# Tx.net
KiCad netlist of a schematic drawn in Altium Designer
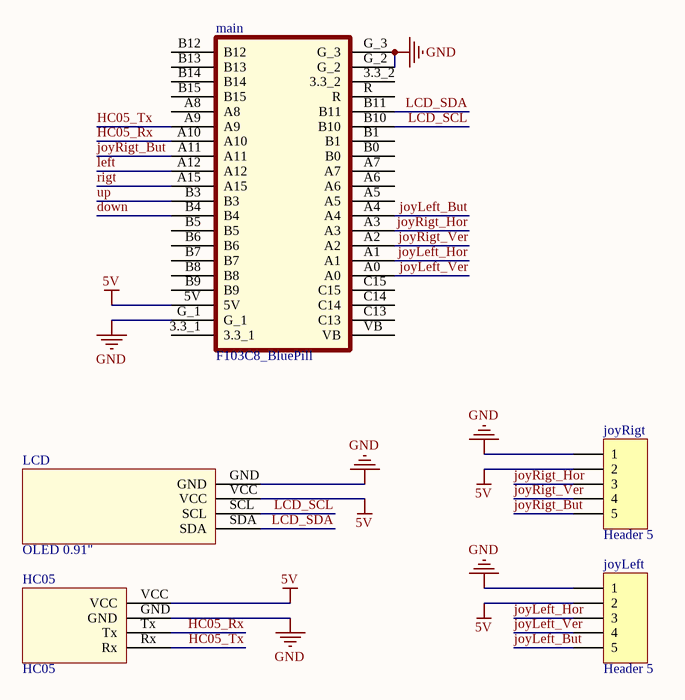
[diagram p0: Tx.SchDoc]

(export (version "E")
  (design (tool "Eeschema 10.0.6"))
  (components
    (comp (ref "HC05") (value "HC05") (footprint "HC05") (libsource (lib "RF-Bluetooth") (part "HC05")))
    (comp (ref "joyLeft")
      (value "Header 5")
      (footprint "HDR1X5")
      (description "Header, 5-Pin")
      (fields (field (name "PUBLISHER") "Altium Limited"))
      (libsource (lib "Miscellaneous Connectors") (part "Header 5"))
    )
    (comp (ref "joyRigt")
      (value "Header 5")
      (footprint "HDR1X5")
      (description "Header, 5-Pin")
      (fields (field (name "PUBLISHER") "Altium Limited"))
      (libsource (lib "Miscellaneous Connectors") (part "Header 5"))
    )
    (comp (ref "LCD")
      (value "OLED 0.91\"")
      (footprint "OLED 0.91\"")
      (libsource (lib "Screen") (part "OLED 0.91{dblquote}"))
    )
    (comp (ref "main")
      (value "F103C8_BluePill")
      (footprint "F103_BluePill")
      (libsource (lib "STM32KIT") (part "F103C8_BluePill"))
    )
  )
  (nets
    (net (code "1") (name "/HC05_Rx") (class "Default")
      (node (ref "HC05") (pin "Tx") (pinfunction "Tx_Tx") (pintype "passive"))
      (node (ref "main") (pin "A10") (pinfunction "A10_A10") (pintype "passive"))
    )
    (net (code "2") (name "/HC05_Tx") (class "Default")
      (node (ref "HC05") (pin "Rx") (pinfunction "Rx_Rx") (pintype "passive"))
      (node (ref "main") (pin "A9") (pinfunction "A9_A9") (pintype "passive"))
    )
    (net (code "3") (name "/LCD_SCL") (class "Default")
      (node (ref "LCD") (pin "SCL") (pinfunction "SCL_SCL") (pintype "passive"))
      (node (ref "main") (pin "B10") (pinfunction "B10_B10") (pintype "passive"))
    )
    (net (code "4") (name "/LCD_SDA") (class "Default")
      (node (ref "LCD") (pin "SDA") (pinfunction "SDA_SDA") (pintype "passive"))
      (node (ref "main") (pin "B11") (pinfunction "B11_B11") (pintype "passive"))
    )
    (net (code "5") (name "/down") (class "Default")
      (node (ref "main") (pin "B4") (pinfunction "B4_B4") (pintype "passive"))
    )
    (net (code "6") (name "/joyLeft_But") (class "Default")
      (node (ref "joyLeft") (pin "5") (pinfunction "5_5") (pintype "passive"))
      (node (ref "main") (pin "A4") (pinfunction "A4_A4") (pintype "passive"))
    )
    (net (code "7") (name "/joyLeft_Hor") (class "Default")
      (node (ref "joyLeft") (pin "3") (pinfunction "3_3") (pintype "passive"))
      (node (ref "main") (pin "A1") (pinfunction "A1_A1") (pintype "passive"))
    )
    (net (code "8") (name "/joyLeft_Ver") (class "Default")
      (node (ref "joyLeft") (pin "4") (pinfunction "4_4") (pintype "passive"))
      (node (ref "main") (pin "A0") (pinfunction "A0_A0") (pintype "passive"))
    )
    (net (code "9") (name "/joyRigt_But") (class "Default")
      (node (ref "joyRigt") (pin "5") (pinfunction "5_5") (pintype "passive"))
      (node (ref "main") (pin "A11") (pinfunction "A11_A11") (pintype "passive"))
    )
    (net (code "10") (name "/joyRigt_Hor") (class "Default")
      (node (ref "joyRigt") (pin "3") (pinfunction "3_3") (pintype "passive"))
      (node (ref "main") (pin "A3") (pinfunction "A3_A3") (pintype "passive"))
    )
    (net (code "11") (name "/joyRigt_Ver") (class "Default")
      (node (ref "joyRigt") (pin "4") (pinfunction "4_4") (pintype "passive"))
      (node (ref "main") (pin "A2") (pinfunction "A2_A2") (pintype "passive"))
    )
    (net (code "12") (name "/left") (class "Default")
      (node (ref "main") (pin "A12") (pinfunction "A12_A12") (pintype "passive"))
    )
    (net (code "13") (name "/rigt") (class "Default")
      (node (ref "main") (pin "A15") (pinfunction "A15_A15") (pintype "passive"))
    )
    (net (code "14") (name "/up") (class "Default")
      (node (ref "main") (pin "B3") (pinfunction "B3_B3") (pintype "passive"))
    )
    (net (code "15") (name "5V") (class "Default")
      (node (ref "HC05") (pin "VCC") (pinfunction "VCC_VCC") (pintype "passive"))
      (node (ref "LCD") (pin "VCC") (pinfunction "VCC_VCC") (pintype "passive"))
      (node (ref "joyLeft") (pin "2") (pinfunction "2_2") (pintype "passive"))
      (node (ref "joyRigt") (pin "2") (pinfunction "2_2") (pintype "passive"))
      (node (ref "main") (pin "5V") (pinfunction "5V_5V") (pintype "passive"))
    )
    (net (code "16") (name "GND") (class "Default")
      (node (ref "HC05") (pin "GND") (pinfunction "GND_GND") (pintype "passive"))
      (node (ref "LCD") (pin "GND") (pinfunction "GND_GND") (pintype "passive"))
      (node (ref "joyLeft") (pin "1") (pinfunction "1_1") (pintype "passive"))
      (node (ref "joyRigt") (pin "1") (pinfunction "1_1") (pintype "passive"))
      (node (ref "main") (pin "G_1") (pinfunction "G_1_G_1") (pintype "passive"))
      (node (ref "main") (pin "G_2") (pinfunction "G_2_G_2") (pintype "passive"))
      (node (ref "main") (pin "G_3") (pinfunction "G_3_G_3") (pintype "passive"))
    )
    (net (code "17") (name "unconnected-(main-Pad3.3_1)") (class "Default")
      (node (ref "main") (pin "3.3_1") (pinfunction "3.3_1_3.3_1") (pintype "passive"))
    )
    (net (code "18") (name "unconnected-(main-Pad3.3_2)") (class "Default")
      (node (ref "main") (pin "3.3_2") (pinfunction "3.3_2_3.3_2") (pintype "passive"))
    )
    (net (code "19") (name "unconnected-(main-PadA5)") (class "Default")
      (node (ref "main") (pin "A5") (pinfunction "A5_A5") (pintype "passive"))
    )
    (net (code "20") (name "unconnected-(main-PadA6)") (class "Default")
      (node (ref "main") (pin "A6") (pinfunction "A6_A6") (pintype "passive"))
    )
    (net (code "21") (name "unconnected-(main-PadA7)") (class "Default")
      (node (ref "main") (pin "A7") (pinfunction "A7_A7") (pintype "passive"))
    )
    (net (code "22") (name "unconnected-(main-PadA8)") (class "Default")
      (node (ref "main") (pin "A8") (pinfunction "A8_A8") (pintype "passive"))
    )
    (net (code "23") (name "unconnected-(main-PadB0)") (class "Default")
      (node (ref "main") (pin "B0") (pinfunction "B0_B0") (pintype "passive"))
    )
    (net (code "24") (name "unconnected-(main-PadB1)") (class "Default")
      (node (ref "main") (pin "B1") (pinfunction "B1_B1") (pintype "passive"))
    )
    (net (code "25") (name "unconnected-(main-PadB5)") (class "Default")
      (node (ref "main") (pin "B5") (pinfunction "B5_B5") (pintype "passive"))
    )
    (net (code "26") (name "unconnected-(main-PadB6)") (class "Default")
      (node (ref "main") (pin "B6") (pinfunction "B6_B6") (pintype "passive"))
    )
    (net (code "27") (name "unconnected-(main-PadB7)") (class "Default")
      (node (ref "main") (pin "B7") (pinfunction "B7_B7") (pintype "passive"))
    )
    (net (code "28") (name "unconnected-(main-PadB8)") (class "Default")
      (node (ref "main") (pin "B8") (pinfunction "B8_B8") (pintype "passive"))
    )
    (net (code "29") (name "unconnected-(main-PadB9)") (class "Default")
      (node (ref "main") (pin "B9") (pinfunction "B9_B9") (pintype "passive"))
    )
    (net (code "30") (name "unconnected-(main-PadB12)") (class "Default")
      (node (ref "main") (pin "B12") (pinfunction "B12_B12") (pintype "passive"))
    )
    (net (code "31") (name "unconnected-(main-PadB13)") (class "Default")
      (node (ref "main") (pin "B13") (pinfunction "B13_B13") (pintype "passive"))
    )
    (net (code "32") (name "unconnected-(main-PadB14)") (class "Default")
      (node (ref "main") (pin "B14") (pinfunction "B14_B14") (pintype "passive"))
    )
    (net (code "33") (name "unconnected-(main-PadB15)") (class "Default")
      (node (ref "main") (pin "B15") (pinfunction "B15_B15") (pintype "passive"))
    )
    (net (code "34") (name "unconnected-(main-PadC13)") (class "Default")
      (node (ref "main") (pin "C13") (pinfunction "C13_C13") (pintype "passive"))
    )
    (net (code "35") (name "unconnected-(main-PadC14)") (class "Default")
      (node (ref "main") (pin "C14") (pinfunction "C14_C14") (pintype "passive"))
    )
    (net (code "36") (name "unconnected-(main-PadC15)") (class "Default")
      (node (ref "main") (pin "C15") (pinfunction "C15_C15") (pintype "passive"))
    )
    (net (code "37") (name "unconnected-(main-PadR)") (class "Default")
      (node (ref "main") (pin "R") (pinfunction "R_R") (pintype "passive"))
    )
    (net (code "38") (name "unconnected-(main-PadVB)") (class "Default")
      (node (ref "main") (pin "VB") (pinfunction "VB_VB") (pintype "passive"))
    )
  )
)
